# RPCamV2_Alt_camera_board.net
KiCad netlist of a schematic drawn in EAGLE
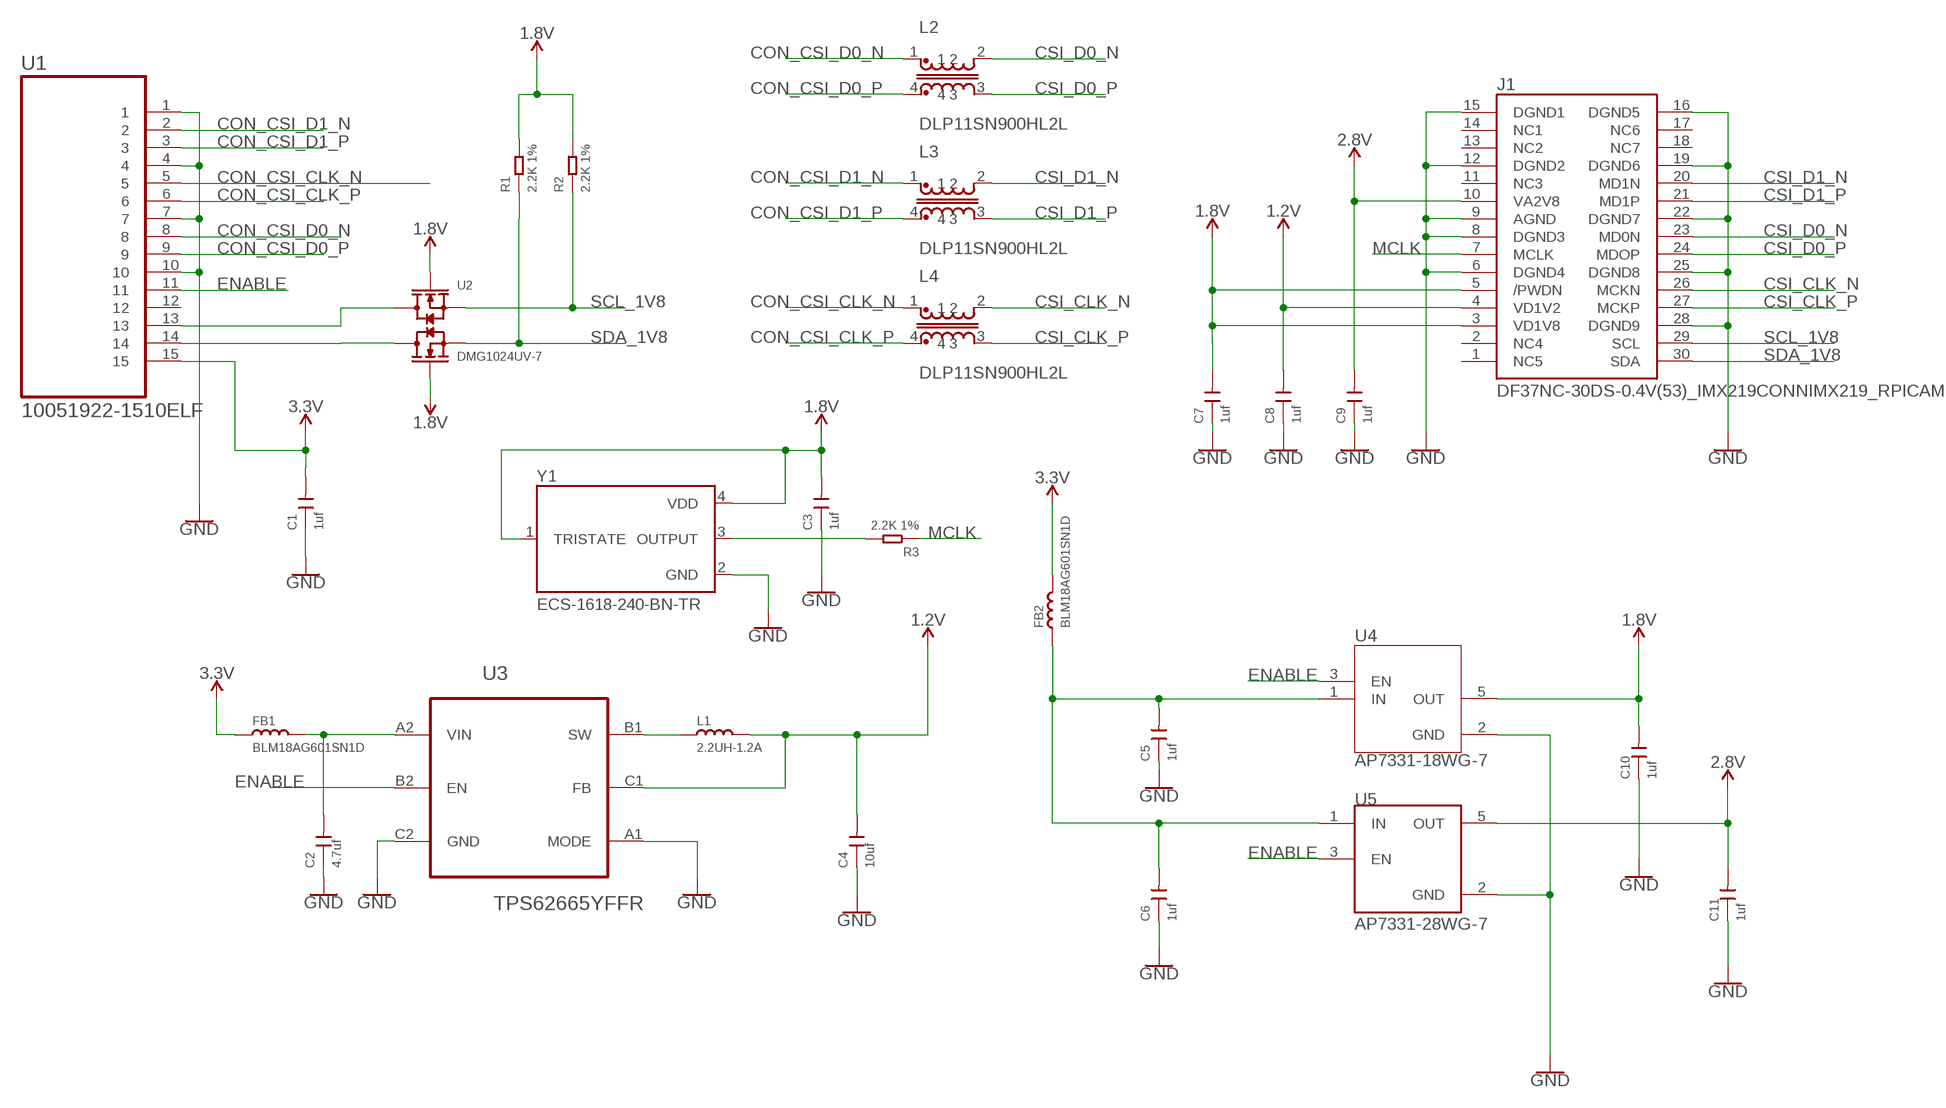
[diagram p0: schematic, sheet 1]

(export (version "E")
  (design (tool "Eeschema 10.0.6"))
  (components
    (comp (ref "C1")
      (value "1uf")
      (footprint "eagle-import:C0402")
      (fields (field (name "MPN") "CC0402KRX5R6BB105"))
      (libsource (lib "eagle-import") (part "CERAMIC-1UF-10V-10%-X5R(0402)"))
    )
    (comp (ref "C2")
      (value "4.7uf")
      (footprint "eagle-import:C0603")
      (fields (field (name "MPN") "CC0603KRX5R6BB475"))
      (libsource (lib "eagle-import") (part "CERAMIC-4.7UF-10V-10%-X5R(0603)"))
    )
    (comp (ref "C3")
      (value "1uf")
      (footprint "eagle-import:C0402")
      (fields (field (name "MPN") "CC0402KRX5R6BB105"))
      (libsource (lib "eagle-import") (part "CERAMIC-1UF-10V-10%-X5R(0402)"))
    )
    (comp (ref "C4")
      (value "10uf")
      (footprint "eagle-import:C0805")
      (fields (field (name "MPN") "CC0805KKX5R8BB106"))
      (libsource (lib "eagle-import") (part "CERAMIC-10UF-25V-10%-X5R(0805)"))
    )
    (comp (ref "C5")
      (value "1uf")
      (footprint "eagle-import:C0402")
      (fields (field (name "MPN") "CC0402KRX5R6BB105"))
      (libsource (lib "eagle-import") (part "CERAMIC-1UF-10V-10%-X5R(0402)"))
    )
    (comp (ref "C6")
      (value "1uf")
      (footprint "eagle-import:C0402")
      (fields (field (name "MPN") "CC0402KRX5R6BB105"))
      (libsource (lib "eagle-import") (part "CERAMIC-1UF-10V-10%-X5R(0402)"))
    )
    (comp (ref "C7")
      (value "1uf")
      (footprint "eagle-import:C0402")
      (fields (field (name "MPN") "CC0402KRX5R6BB105"))
      (libsource (lib "eagle-import") (part "CERAMIC-1UF-10V-10%-X5R(0402)"))
    )
    (comp (ref "C8")
      (value "1uf")
      (footprint "eagle-import:C0402")
      (fields (field (name "MPN") "CC0402KRX5R6BB105"))
      (libsource (lib "eagle-import") (part "CERAMIC-1UF-10V-10%-X5R(0402)"))
    )
    (comp (ref "C9")
      (value "1uf")
      (footprint "eagle-import:C0402")
      (fields (field (name "MPN") "CC0402KRX5R6BB105"))
      (libsource (lib "eagle-import") (part "CERAMIC-1UF-10V-10%-X5R(0402)"))
    )
    (comp (ref "C10")
      (value "1uf")
      (footprint "eagle-import:C0402")
      (fields (field (name "MPN") "CC0402KRX5R6BB105"))
      (libsource (lib "eagle-import") (part "CERAMIC-1UF-10V-10%-X5R(0402)"))
    )
    (comp (ref "C11")
      (value "1uf")
      (footprint "eagle-import:C0402")
      (fields (field (name "MPN") "CC0402KRX5R6BB105"))
      (libsource (lib "eagle-import") (part "CERAMIC-1UF-10V-10%-X5R(0402)"))
    )
    (comp (ref "FB1")
      (value "BLM18AG601SN1D")
      (footprint "eagle-import:LEDM1608X80")
      (libsource (lib "eagle-import") (part "BLM18AG601SN1D"))
    )
    (comp (ref "FB2")
      (value "BLM18AG601SN1D")
      (footprint "eagle-import:LEDM1608X80")
      (libsource (lib "eagle-import") (part "BLM18AG601SN1D"))
    )
    (comp (ref "J1")
      (value "DF37NC-30DS-0.4V(53)_IMX219CONNIMX219_RPICAM")
      (footprint "eagle-import:HRS_DF37NC-30DS-0.4V(53)_IMX219")
      (libsource (lib "eagle-import") (part "DF37NC-30DS-0.4V(53)_IMX219CONNIMX219_RPICAM"))
    )
    (comp (ref "L1")
      (value "2.2UH-1.2A")
      (footprint "eagle-import:L0805")
      (fields (field (name "MPN") "LQM2MPN2R2MG0"))
      (libsource (lib "eagle-import") (part "SMD-INDUCTOR-2.2UH-20%-1.2A(0805)"))
    )
    (comp (ref "L2")
      (value "DLP11SN900HL2L")
      (footprint "eagle-import:INDC1210X09")
      (fields (field (name "MF") "Murata"))
      (libsource (lib "eagle-import") (part "DLP11SN900HL2L"))
    )
    (comp (ref "L3")
      (value "DLP11SN900HL2L")
      (footprint "eagle-import:INDC1210X09")
      (fields (field (name "MF") "Murata"))
      (libsource (lib "eagle-import") (part "DLP11SN900HL2L"))
    )
    (comp (ref "L4")
      (value "DLP11SN900HL2L")
      (footprint "eagle-import:INDC1210X09")
      (fields (field (name "MF") "Murata"))
      (libsource (lib "eagle-import") (part "DLP11SN900HL2L"))
    )
    (comp (ref "R1")
      (value "2.2K 1%")
      (footprint "eagle-import:R0402")
      (fields (field (name "MPN") "RC0402JR-070RL"))
      (libsource (lib "eagle-import") (part "SMD-RES-0R-5%-1/16W(0402)"))
    )
    (comp (ref "R2")
      (value "2.2K 1%")
      (footprint "eagle-import:R0402")
      (fields (field (name "MPN") "RC0402JR-070RL"))
      (libsource (lib "eagle-import") (part "SMD-RES-0R-5%-1/16W(0402)"))
    )
    (comp (ref "R3")
      (value "2.2K 1%")
      (footprint "eagle-import:R0402")
      (fields (field (name "MPN") "RC0402JR-070RL"))
      (libsource (lib "eagle-import") (part "SMD-RES-0R-5%-1/16W(0402)"))
    )
    (comp (ref "U1")
      (value "10051922-1510ELF")
      (footprint "eagle-import:FCI_10051922-1510ELF")
      (fields (field (name "MF") "FCI"))
      (libsource (lib "eagle-import") (part "10051922-1510ELF"))
    )
    (comp (ref "U2")
      (value "DMG1024UV-7")
      (footprint "eagle-import:SOT50P162X60-6N")
      (fields (field (name "MF") "Diodes Inc."))
      (libsource (lib "eagle-import") (part "DMG1024UV-7"))
    )
    (comp (ref "U3")
      (value "TPS62665YFFR")
      (footprint "eagle-import:BGA6C40P2X3_130X93X63")
      (fields (field (name "MF") "Texas Instruments"))
      (libsource (lib "eagle-import") (part "TPS62665YFFR"))
    )
    (comp (ref "U4")
      (value "AP7331-18WG-7")
      (footprint "eagle-import:SOT95P285X145-5N")
      (fields (field (name "MF") "Diodes Inc."))
      (libsource (lib "eagle-import") (part "AP7331-18WG-7"))
    )
    (comp (ref "U5")
      (value "AP7331-28WG-7")
      (footprint "eagle-import:SOT95P285X145-5N")
      (fields (field (name "MF") "Diodes Inc."))
      (libsource (lib "eagle-import") (part "AP7331-28WG-7"))
    )
    (comp (ref "Y1")
      (value "ECS-1618-240-BN-TR")
      (footprint "eagle-import:XTAL_ECS-1618-060-BN-TR")
      (fields (field (name "DIGI-KEY_PART_NUMBER") "XC1963CT-ND") (field (name "MF") "ECS International"))
      (libsource (lib "eagle-import") (part "ECS-1618-240-BN-TR"))
    )
  )
  (nets
    (net (code "1") (name "/CON_CSI_CLK_N") (class "Default")
      (node (ref "L4") (pin "1") (pinfunction "1_1") (pintype "passive"))
      (node (ref "U1") (pin "5") (pinfunction "5_5") (pintype "passive"))
    )
    (net (code "2") (name "/CON_CSI_CLK_P") (class "Default")
      (node (ref "L4") (pin "4") (pinfunction "4_4") (pintype "passive"))
      (node (ref "U1") (pin "6") (pinfunction "6_6") (pintype "passive"))
    )
    (net (code "3") (name "/CON_CSI_D0_N") (class "Default")
      (node (ref "L2") (pin "1") (pinfunction "1_1") (pintype "passive"))
      (node (ref "U1") (pin "8") (pinfunction "8_8") (pintype "passive"))
    )
    (net (code "4") (name "/CON_CSI_D0_P") (class "Default")
      (node (ref "L2") (pin "4") (pinfunction "4_4") (pintype "passive"))
      (node (ref "U1") (pin "9") (pinfunction "9_9") (pintype "passive"))
    )
    (net (code "5") (name "/CON_CSI_D1_N") (class "Default")
      (node (ref "L3") (pin "1") (pinfunction "1_1") (pintype "passive"))
      (node (ref "U1") (pin "2") (pinfunction "2_2") (pintype "passive"))
    )
    (net (code "6") (name "/CON_CSI_D1_P") (class "Default")
      (node (ref "L3") (pin "4") (pinfunction "4_4") (pintype "passive"))
      (node (ref "U1") (pin "3") (pinfunction "3_3") (pintype "passive"))
    )
    (net (code "7") (name "/CSI_CLK_N") (class "Default")
      (node (ref "J1") (pin "26") (pinfunction "MCKN_26") (pintype "passive"))
      (node (ref "L4") (pin "2") (pinfunction "2_2") (pintype "passive"))
    )
    (net (code "8") (name "/CSI_CLK_P") (class "Default")
      (node (ref "J1") (pin "27") (pinfunction "MCKP_27") (pintype "passive"))
      (node (ref "L4") (pin "3") (pinfunction "3_3") (pintype "passive"))
    )
    (net (code "9") (name "/CSI_D0_N") (class "Default")
      (node (ref "J1") (pin "23") (pinfunction "MD0N_23") (pintype "passive"))
      (node (ref "L2") (pin "2") (pinfunction "2_2") (pintype "passive"))
    )
    (net (code "10") (name "/CSI_D0_P") (class "Default")
      (node (ref "J1") (pin "24") (pinfunction "MDOP_24") (pintype "passive"))
      (node (ref "L2") (pin "3") (pinfunction "3_3") (pintype "passive"))
    )
    (net (code "11") (name "/CSI_D1_N") (class "Default")
      (node (ref "J1") (pin "20") (pinfunction "MD1N_20") (pintype "passive"))
      (node (ref "L3") (pin "2") (pinfunction "2_2") (pintype "passive"))
    )
    (net (code "12") (name "/CSI_D1_P") (class "Default")
      (node (ref "J1") (pin "21") (pinfunction "MD1P_21") (pintype "passive"))
      (node (ref "L3") (pin "3") (pinfunction "3_3") (pintype "passive"))
    )
    (net (code "13") (name "/ENABLE") (class "Default")
      (node (ref "U1") (pin "11") (pinfunction "11_11") (pintype "passive"))
      (node (ref "U3") (pin "B2") (pinfunction "EN_B2") (pintype "input"))
      (node (ref "U4") (pin "3") (pinfunction "EN_3") (pintype "input"))
      (node (ref "U5") (pin "3") (pinfunction "EN_3") (pintype "input"))
    )
    (net (code "14") (name "/MCLK") (class "Default")
      (node (ref "J1") (pin "7") (pinfunction "MCLK_7") (pintype "passive"))
      (node (ref "R3") (pin "1") (pinfunction "1_1") (pintype "passive"))
    )
    (net (code "15") (name "/SCL_1V8") (class "Default")
      (node (ref "J1") (pin "29") (pinfunction "SCL_29") (pintype "passive"))
      (node (ref "R2") (pin "1") (pinfunction "1_1") (pintype "passive"))
      (node (ref "U2") (pin "S2") (pinfunction "S1_S2") (pintype "passive"))
    )
    (net (code "16") (name "/SDA_1V8") (class "Default")
      (node (ref "J1") (pin "30") (pinfunction "SDA_30") (pintype "passive"))
      (node (ref "R1") (pin "1") (pinfunction "1_1") (pintype "passive"))
      (node (ref "U2") (pin "S1") (pinfunction "S0_S1") (pintype "passive"))
    )
    (net (code "17") (name "1.2V") (class "Default")
      (node (ref "C4") (pin "2") (pinfunction "2_2") (pintype "passive"))
      (node (ref "C8") (pin "2") (pinfunction "2_2") (pintype "passive"))
      (node (ref "J1") (pin "4") (pinfunction "VD1V2_4") (pintype "passive"))
      (node (ref "L1") (pin "2") (pinfunction "2_2") (pintype "passive"))
      (node (ref "U3") (pin "C1") (pinfunction "FB_C1") (pintype "input"))
    )
    (net (code "18") (name "1.8V") (class "Default")
      (node (ref "C10") (pin "2") (pinfunction "2_2") (pintype "passive"))
      (node (ref "C3") (pin "2") (pinfunction "2_2") (pintype "passive"))
      (node (ref "C7") (pin "2") (pinfunction "2_2") (pintype "passive"))
      (node (ref "J1") (pin "3") (pinfunction "VD1V8_3") (pintype "passive"))
      (node (ref "J1") (pin "5") (pinfunction "/PWDN_5") (pintype "passive"))
      (node (ref "R1") (pin "2") (pinfunction "2_2") (pintype "passive"))
      (node (ref "R2") (pin "2") (pinfunction "2_2") (pintype "passive"))
      (node (ref "U2") (pin "G1") (pinfunction "G0_G1") (pintype "passive"))
      (node (ref "U2") (pin "G2") (pinfunction "G1_G2") (pintype "passive"))
      (node (ref "U4") (pin "5") (pinfunction "OUT_5") (pintype "output"))
      (node (ref "Y1") (pin "1") (pinfunction "TRISTATE_1") (pintype "input"))
      (node (ref "Y1") (pin "4") (pinfunction "VDD_4") (pintype "power_in"))
    )
    (net (code "19") (name "2.8V") (class "Default")
      (node (ref "C11") (pin "2") (pinfunction "2_2") (pintype "passive"))
      (node (ref "C9") (pin "2") (pinfunction "2_2") (pintype "passive"))
      (node (ref "J1") (pin "10") (pinfunction "VA2V8_10") (pintype "passive"))
      (node (ref "U5") (pin "5") (pinfunction "OUT_5") (pintype "output"))
    )
    (net (code "20") (name "3.3V") (class "Default")
      (node (ref "C1") (pin "2") (pinfunction "2_2") (pintype "passive"))
      (node (ref "FB1") (pin "A") (pinfunction "1_A") (pintype "passive"))
      (node (ref "FB2") (pin "C") (pinfunction "2_C") (pintype "passive"))
      (node (ref "U1") (pin "15") (pinfunction "15_15") (pintype "passive"))
    )
    (net (code "21") (name "GND") (class "Default")
      (node (ref "C1") (pin "1") (pinfunction "1_1") (pintype "passive"))
      (node (ref "C10") (pin "1") (pinfunction "1_1") (pintype "passive"))
      (node (ref "C11") (pin "1") (pinfunction "1_1") (pintype "passive"))
      (node (ref "C2") (pin "1") (pinfunction "1_1") (pintype "passive"))
      (node (ref "C3") (pin "1") (pinfunction "1_1") (pintype "passive"))
      (node (ref "C4") (pin "1") (pinfunction "1_1") (pintype "passive"))
      (node (ref "C5") (pin "1") (pinfunction "1_1") (pintype "passive"))
      (node (ref "C6") (pin "1") (pinfunction "1_1") (pintype "passive"))
      (node (ref "C7") (pin "1") (pinfunction "1_1") (pintype "passive"))
      (node (ref "C8") (pin "1") (pinfunction "1_1") (pintype "passive"))
      (node (ref "C9") (pin "1") (pinfunction "1_1") (pintype "passive"))
      (node (ref "J1") (pin "12") (pinfunction "DGND2_12") (pintype "passive"))
      (node (ref "J1") (pin "15") (pinfunction "DGND1_15") (pintype "passive"))
      (node (ref "J1") (pin "16") (pinfunction "DGND5_16") (pintype "passive"))
      (node (ref "J1") (pin "19") (pinfunction "DGND6_19") (pintype "passive"))
      (node (ref "J1") (pin "22") (pinfunction "DGND7_22") (pintype "passive"))
      (node (ref "J1") (pin "25") (pinfunction "DGND8_25") (pintype "passive"))
      (node (ref "J1") (pin "28") (pinfunction "DGND9_28") (pintype "passive"))
      (node (ref "J1") (pin "6") (pinfunction "DGND4_6") (pintype "passive"))
      (node (ref "J1") (pin "8") (pinfunction "DGND3_8") (pintype "passive"))
      (node (ref "J1") (pin "9") (pinfunction "AGND_9") (pintype "passive"))
      (node (ref "U1") (pin "1") (pinfunction "1_1") (pintype "passive"))
      (node (ref "U1") (pin "10") (pinfunction "10_10") (pintype "passive"))
      (node (ref "U1") (pin "4") (pinfunction "4_4") (pintype "passive"))
      (node (ref "U1") (pin "7") (pinfunction "7_7") (pintype "passive"))
      (node (ref "U3") (pin "A1") (pinfunction "MODE_A1") (pintype "input"))
      (node (ref "U3") (pin "C2") (pinfunction "GND_C2") (pintype "passive"))
      (node (ref "U4") (pin "2") (pinfunction "GND_2") (pintype "power_in"))
      (node (ref "U5") (pin "2") (pinfunction "GND_2") (pintype "power_in"))
      (node (ref "Y1") (pin "2") (pinfunction "GND_2") (pintype "power_in"))
    )
    (net (code "22") (name "Net-(FB1-2)") (class "Default")
      (node (ref "C2") (pin "2") (pinfunction "2_2") (pintype "passive"))
      (node (ref "FB1") (pin "C") (pinfunction "2_C") (pintype "passive"))
      (node (ref "U3") (pin "A2") (pinfunction "VIN_A2") (pintype "power_in"))
    )
    (net (code "23") (name "Net-(FB2-1)") (class "Default")
      (node (ref "C5") (pin "2") (pinfunction "2_2") (pintype "passive"))
      (node (ref "C6") (pin "2") (pinfunction "2_2") (pintype "passive"))
      (node (ref "FB2") (pin "A") (pinfunction "1_A") (pintype "passive"))
      (node (ref "U4") (pin "1") (pinfunction "IN_1") (pintype "input"))
      (node (ref "U5") (pin "1") (pinfunction "IN_1") (pintype "input"))
    )
    (net (code "24") (name "Net-(U2-D0)") (class "Default")
      (node (ref "U1") (pin "14") (pinfunction "14_14") (pintype "passive"))
      (node (ref "U2") (pin "D1") (pinfunction "D0_D1") (pintype "passive"))
    )
    (net (code "25") (name "Net-(U2-D1)") (class "Default")
      (node (ref "U1") (pin "13") (pinfunction "13_13") (pintype "passive"))
      (node (ref "U2") (pin "D2") (pinfunction "D1_D2") (pintype "passive"))
    )
    (net (code "26") (name "Net-(U3-SW)") (class "Default")
      (node (ref "L1") (pin "1") (pinfunction "1_1") (pintype "passive"))
      (node (ref "U3") (pin "B1") (pinfunction "SW_B1") (pintype "bidirectional"))
    )
    (net (code "27") (name "Net-(Y1-OUTPUT)") (class "Default")
      (node (ref "R3") (pin "2") (pinfunction "2_2") (pintype "passive"))
      (node (ref "Y1") (pin "3") (pinfunction "OUTPUT_3") (pintype "output"))
    )
    (net (code "28") (name "unconnected-(J1-NC1-Pad14)") (class "Default")
      (node (ref "J1") (pin "14") (pinfunction "NC1_14") (pintype "passive"))
    )
    (net (code "29") (name "unconnected-(J1-NC2-Pad13)") (class "Default")
      (node (ref "J1") (pin "13") (pinfunction "NC2_13") (pintype "passive"))
    )
    (net (code "30") (name "unconnected-(J1-NC3-Pad11)") (class "Default")
      (node (ref "J1") (pin "11") (pinfunction "NC3_11") (pintype "passive"))
    )
    (net (code "31") (name "unconnected-(J1-NC4-Pad2)") (class "Default")
      (node (ref "J1") (pin "2") (pinfunction "NC4_2") (pintype "passive"))
    )
    (net (code "32") (name "unconnected-(J1-NC5-Pad1)") (class "Default")
      (node (ref "J1") (pin "1") (pinfunction "NC5_1") (pintype "passive"))
    )
    (net (code "33") (name "unconnected-(J1-NC6-Pad17)") (class "Default")
      (node (ref "J1") (pin "17") (pinfunction "NC6_17") (pintype "passive"))
    )
    (net (code "34") (name "unconnected-(J1-NC7-Pad18)") (class "Default")
      (node (ref "J1") (pin "18") (pinfunction "NC7_18") (pintype "passive"))
    )
    (net (code "35") (name "unconnected-(U1-Pad12)") (class "Default")
      (node (ref "U1") (pin "12") (pinfunction "12_12") (pintype "passive"))
    )
  )
)
